# Power.net
KiCad netlist of a schematic drawn in Altium Designer
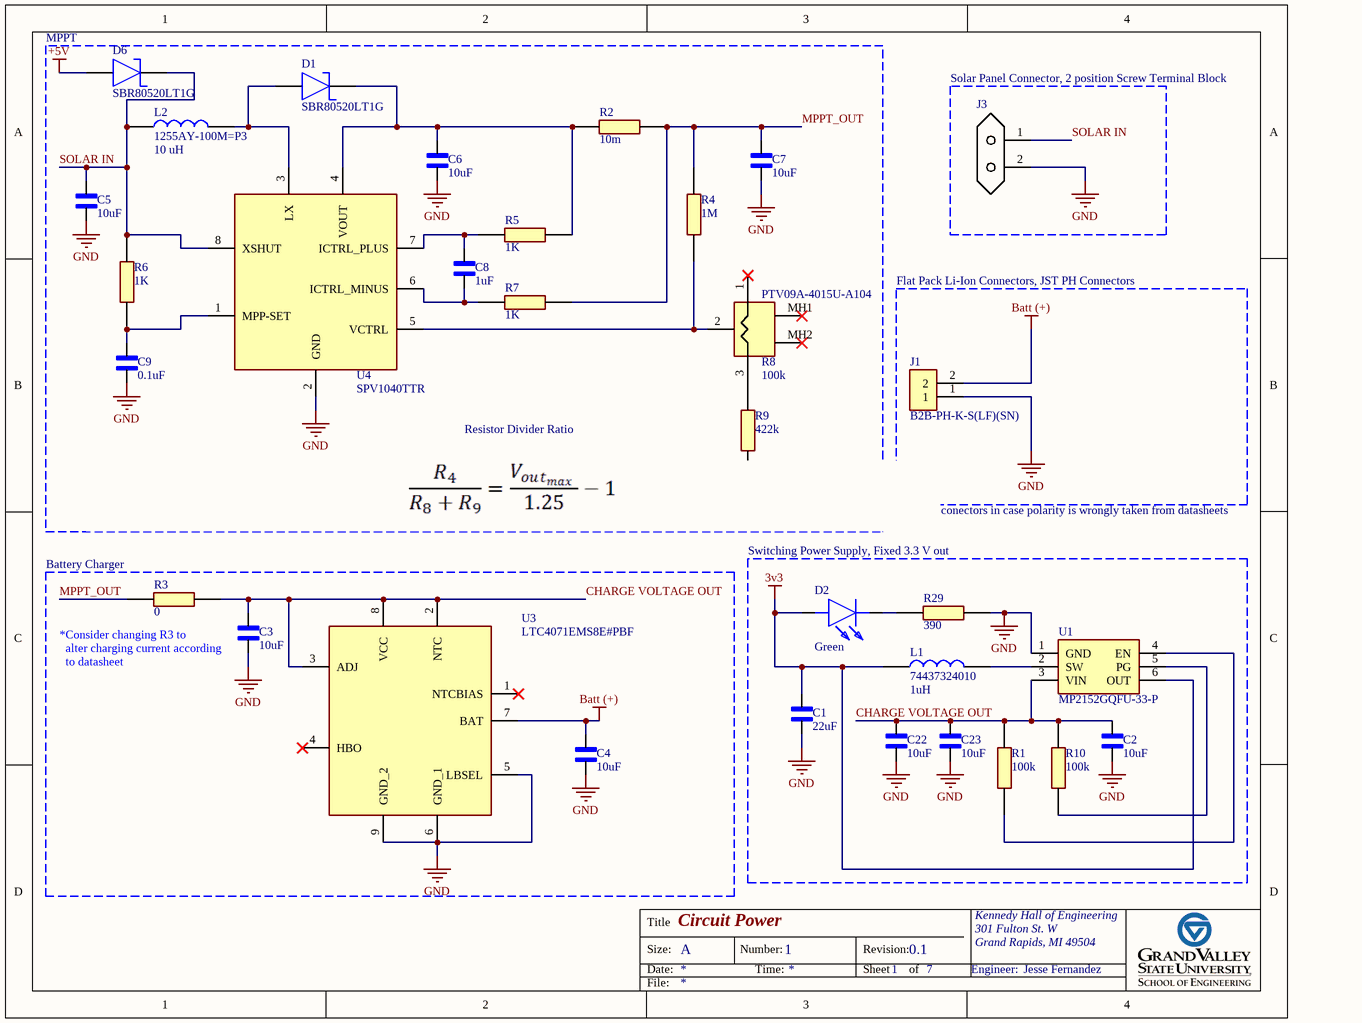
[diagram p0: Power.SchDoc]

(export (version "E")
  (design (tool "Eeschema 10.0.6"))
  (components
    (comp (ref "C1")
      (value "22uF")
      (footprint "CAPC1005X55N")
      (description "Capacitor X6S 0402 (1005 Metric)")
      (fields (field (name "MANUFACTURER") "Samsung Electro-Mechanics") (field (name "TOLERANCE") "20%"))
      (libsource (lib "UngBung") (part "Multilayer Ceramic Cap. 0402 (1005 Metric)"))
    )
    (comp (ref "C2")
      (value "10uF")
      (footprint "CAPC1005X55N")
      (description "Capacitor X6S 0402 (1005 Metric)")
      (fields (field (name "MANUFACTURER") "Murata Electronics") (field (name "TOLERANCE") "20%"))
      (libsource (lib "UngBung") (part "Multilayer Ceramic Cap. 0402 (1005 Metric)"))
    )
    (comp (ref "C3")
      (value "10uF")
      (footprint "CAPC1005X55N")
      (description "Capacitor X6S 0402 (1005 Metric)")
      (fields (field (name "MANUFACTURER") "Murata Electronics") (field (name "TOLERANCE") "20%"))
      (libsource (lib "UngBung") (part "Multilayer Ceramic Cap. 0402 (1005 Metric)"))
    )
    (comp (ref "C4")
      (value "10uF")
      (footprint "CAPC1005X55N")
      (description "Capacitor X6S 0402 (1005 Metric)")
      (fields (field (name "MANUFACTURER") "Murata Electronics") (field (name "TOLERANCE") "20%"))
      (libsource (lib "UngBung") (part "Multilayer Ceramic Cap. 0402 (1005 Metric)"))
    )
    (comp (ref "C5")
      (value "10uF")
      (footprint "CAPC1005X55N")
      (description "Capacitor X6S 0402 (1005 Metric)")
      (fields (field (name "MANUFACTURER") "Murata Electronics") (field (name "TOLERANCE") "20%"))
      (libsource (lib "UngBung") (part "Multilayer Ceramic Cap. 0402 (1005 Metric)"))
    )
    (comp (ref "C6")
      (value "10uF")
      (footprint "CAPC1005X55N")
      (description "Capacitor X6S 0402 (1005 Metric)")
      (fields (field (name "MANUFACTURER") "Murata Electronics") (field (name "TOLERANCE") "20%"))
      (libsource (lib "UngBung") (part "Multilayer Ceramic Cap. 0402 (1005 Metric)"))
    )
    (comp (ref "C7")
      (value "10uF")
      (footprint "CAPC1005X55N")
      (description "Capacitor X6S 0402 (1005 Metric)")
      (fields (field (name "MANUFACTURER") "Murata Electronics") (field (name "TOLERANCE") "20%"))
      (libsource (lib "UngBung") (part "Multilayer Ceramic Cap. 0402 (1005 Metric)"))
    )
    (comp (ref "C8")
      (value "1uF")
      (footprint "CAPC1005X55N")
      (description "Capacitor X6S 0402 (1005 Metric)")
      (fields (field (name "MANUFACTURER") "Murata Electronics") (field (name "TOLERANCE") "10%"))
      (libsource (lib "UngBung") (part "Multilayer Ceramic Cap. 0402 (1005 Metric)"))
    )
    (comp (ref "C9")
      (value "0.1uF")
      (footprint "CAPC1005X55N")
      (description "Capacitor X6S 0402 (1005 Metric)")
      (fields (field (name "MANUFACTURER") "Murata Electronics") (field (name "TOLERANCE") "10%"))
      (libsource (lib "UngBung") (part "Multilayer Ceramic Cap. 0402 (1005 Metric)"))
    )
    (comp (ref "C22")
      (value "10uF")
      (footprint "CAPC1005X55N")
      (description "Capacitor X6S 0402 (1005 Metric)")
      (fields (field (name "MANUFACTURER") "Murata Electronics") (field (name "TOLERANCE") "20%"))
      (libsource (lib "UngBung") (part "Multilayer Ceramic Cap. 0402 (1005 Metric)"))
    )
    (comp (ref "C23")
      (value "10uF")
      (footprint "CAPC1005X55N")
      (description "Capacitor X6S 0402 (1005 Metric)")
      (fields (field (name "MANUFACTURER") "Murata Electronics") (field (name "TOLERANCE") "20%"))
      (libsource (lib "UngBung") (part "Multilayer Ceramic Cap. 0402 (1005 Metric)"))
    )
    (comp (ref "D1")
      (value "SBR80520LT1G")
      (footprint "Diode SOD-123-2")
      (description "Schottky Diodes & Rectifiers REC SPCL SKTKY")
      (fields (field (name "MANUFACTURER") "ON Semiconductor"))
      (libsource (lib "UngBung") (part "SBR80520LT1G"))
    )
    (comp (ref "D2")
      (value "SML-LX0201UPGC-TR")
      (footprint "SML-LX0201UPGC-TR")
      (description "Standard LEDs - SMD 0201 SMD LEDs 520nm Green")
      (fields (field (name "MANUFACTURER") "Lumex") (field (name "COLOR") "Green"))
      (libsource (lib "UngBung") (part "SML-LX0201UPGC-TR"))
    )
    (comp (ref "D6")
      (value "SBR80520LT1G")
      (footprint "Diode SOD-123-2")
      (description "Schottky Diodes & Rectifiers REC SPCL SKTKY")
      (fields (field (name "MANUFACTURER") "ON Semiconductor"))
      (libsource (lib "UngBung") (part "SBR80520LT1G"))
    )
    (comp (ref "J1")
      (value "B2B-PH-K-S(LF)(SN)")
      (footprint "B2B-PH-K-S(LF)(SN)")
      (description "Connector Header Through Hole 2 position 0.079\" (2.00mm)")
      (fields (field (name "MANUFACTURER") "JST Sales America Inc."))
      (libsource (lib "UngBung") (part "B2B-PH-K-S(LF)(SN)"))
    )
    (comp (ref "J3")
      (value "Two-Position Terminal Block")
      (footprint "TB001-500-02BE")
      (fields (field (name "MANUFACTURER") "CUI Devices"))
      (libsource (lib "UngBung") (part "TB001-500-02BE"))
    )
    (comp (ref "L1")
      (value "74437324010")
      (footprint "Shielded Power Inductor")
      (description "Shieled Power Inductor")
      (fields (field (name "MANUFACTURER") "Wurth Elektronik") (field (name "ALTIUM_VALUE") "1uH"))
      (libsource (lib "UngBung") (part "74437324010"))
    )
    (comp (ref "L2")
      (value "1255AY-100M=P3")
      (footprint "1255AY-100M=P3")
      (description "Fixed Inductors 10uH 56.4mOhms3.1A +/-20% 6.3x6.3x4.5mm")
      (fields (field (name "MANUFACTURER") "Murata Electronics") (field (name "ALTIUM_VALUE") "10 uH"))
      (libsource (lib "UngBung") (part "1255AY-100M=P3"))
    )
    (comp (ref "R1")
      (value "100k")
      (footprint "Thin-Film Resistor 0402 (1005 Metric)")
      (description "Resistor, 0402 Package size")
      (fields (field (name "MANUFACTURER") "Vishay / Dale") (field (name "TOLERANCE") "1%"))
      (libsource (lib "UngBung") (part "Resistor 0402 (1005 Metric)"))
    )
    (comp (ref "R2")
      (value "10m")
      (footprint "Thin-Film Resistor 0402 (1005 Metric)")
      (description "Resistor, 0402 Package size")
      (fields (field (name "MANUFACTURER") "Panasonic") (field (name "TOLERANCE") "1%"))
      (libsource (lib "") (part "Resistor 0402 (1005 Metric)_1"))
    )
    (comp (ref "R3")
      (value "0")
      (footprint "Resistor 0603")
      (fields
        (field (name "MANUFACTURER") "Vishay / Dale")
        (field (name "TOLERANCE") "*tolerance*")
        (field (name "Comment") "Resistor 0603")
      )
      (libsource (lib "UngBung") (part "Resistor 0603"))
    )
    (comp (ref "R4")
      (value "1M")
      (footprint "Thin-Film Resistor 0402 (1005 Metric)")
      (description "Resistor, 0402 Package size")
      (fields (field (name "MANUFACTURER") "Vishay / Dale") (field (name "TOLERANCE") "1%"))
      (libsource (lib "UngBung") (part "Resistor 0402 (1005 Metric)"))
    )
    (comp (ref "R5")
      (value "1K")
      (footprint "Thin-Film Resistor 0402 (1005 Metric)")
      (description "Resistor, 0402 Package size")
      (fields (field (name "MANUFACTURER") "Vishay / Dale") (field (name "TOLERANCE") "1%"))
      (libsource (lib "") (part "Resistor 0402 (1005 Metric)_2"))
    )
    (comp (ref "R6")
      (value "1K")
      (footprint "Thin-Film Resistor 0402 (1005 Metric)")
      (description "Resistor, 0402 Package size")
      (fields (field (name "MANUFACTURER") "Vishay / Dale") (field (name "TOLERANCE") "1%"))
      (libsource (lib "UngBung") (part "Resistor 0402 (1005 Metric)"))
    )
    (comp (ref "R7")
      (value "1K")
      (footprint "Thin-Film Resistor 0402 (1005 Metric)")
      (description "Resistor, 0402 Package size")
      (fields (field (name "MANUFACTURER") "Vishay / Dale") (field (name "TOLERANCE") "1%"))
      (libsource (lib "") (part "Resistor 0402 (1005 Metric)_2"))
    )
    (comp (ref "R8")
      (value "PTV09A-4015U-A104")
      (footprint "PTV09A-4015U-A104")
      (description "Potentiometers PANEL CONTROL - 9MM-ST-CA 100 kohms 15 mm")
      (fields (field (name "MANUFACTURER") "Bourns") (field (name "ALTIUM_VALUE") "100k"))
      (libsource (lib "UngBung") (part "PTV09A-4015U-A104"))
    )
    (comp (ref "R9")
      (value "422k")
      (footprint "Thin-Film Resistor 0402 (1005 Metric)")
      (description "Resistor, 0402 Package size")
      (fields (field (name "MANUFACTURER") "Panasonic") (field (name "TOLERANCE") "1%"))
      (libsource (lib "UngBung") (part "Resistor 0402 (1005 Metric)"))
    )
    (comp (ref "R10")
      (value "100k")
      (footprint "Thin-Film Resistor 0402 (1005 Metric)")
      (description "Resistor, 0402 Package size")
      (fields (field (name "MANUFACTURER") "Vishay / Dale") (field (name "TOLERANCE") "1%"))
      (libsource (lib "UngBung") (part "Resistor 0402 (1005 Metric)"))
    )
    (comp (ref "R29")
      (value "390")
      (footprint "Thin-Film Resistor 0402 (1005 Metric)")
      (description "Resistor, 0402 Package size")
      (fields (field (name "MANUFACTURER") "Yageo") (field (name "TOLERANCE") "1%"))
      (libsource (lib "") (part "Resistor 0402 (1005 Metric)_1"))
    )
    (comp (ref "U1")
      (value "MP2152GQFU-33-P")
      (footprint "MP2152GQFU-33-P")
      (fields (field (name "MANUFACTURER") "Monolithic Power Systems (MPS)"))
      (libsource (lib "UngBung") (part "MP2152GQFU-33-P"))
    )
    (comp (ref "U3")
      (value "LTC4071EMS8E#PBF")
      (footprint "LTC4071EMS8E#PBF")
      (description "Battery Management Li-Ion/Polymer Shunt Battery Charger System with Low Battery Disconnect")
      (fields (field (name "MANUFACTURER") "Analog Devices"))
      (libsource (lib "UngBung") (part "LTC4071EMS8E#PBF"))
    )
    (comp (ref "U4")
      (value "SPV1040TTR")
      (footprint "SPV1040TTR")
      (description "Switching Voltage Regulators Hi Eff Solar Charger MPPT 0.3V to 5.5V")
      (fields (field (name "MANUFACTURER") "STMicroelectronics"))
      (libsource (lib "UngBung") (part "SPV1040TTR"))
    )
  )
  (nets
    (net (code "1") (name "+5V") (class "Default")
      (node (ref "D6") (pin "2") (pinfunction "A_2") (pintype "passive"))
    )
    (net (code "3") (name "/CHARGE VOLTAGE OUT") (class "Default")
      (node (ref "C2") (pin "2") (pinfunction "2_2") (pintype "passive"))
      (node (ref "C22") (pin "2") (pinfunction "2_2") (pintype "passive"))
      (node (ref "C23") (pin "2") (pinfunction "2_2") (pintype "passive"))
      (node (ref "C3") (pin "2") (pinfunction "2_2") (pintype "passive"))
      (node (ref "R1") (pin "2") (pinfunction "2_2") (pintype "passive"))
      (node (ref "R10") (pin "2") (pinfunction "2_2") (pintype "passive"))
      (node (ref "R3") (pin "2") (pinfunction "2_2") (pintype "passive"))
      (node (ref "U1") (pin "3") (pinfunction "VIN_3") (pintype "passive"))
      (node (ref "U3") (pin "2") (pinfunction "NTC_2") (pintype "passive"))
      (node (ref "U3") (pin "3") (pinfunction "ADJ_3") (pintype "passive"))
      (node (ref "U3") (pin "8") (pinfunction "VCC_8") (pintype "passive"))
    )
    (net (code "4") (name "/MPPT_OUT") (class "Default")
      (node (ref "C7") (pin "2") (pinfunction "2_2") (pintype "passive"))
      (node (ref "R2") (pin "2") (pinfunction "2_2") (pintype "passive"))
      (node (ref "R3") (pin "1") (pinfunction "1_1") (pintype "passive"))
      (node (ref "R4") (pin "2") (pinfunction "2_2") (pintype "passive"))
      (node (ref "R7") (pin "1") (pinfunction "1_1") (pintype "passive"))
    )
    (net (code "5") (name "/SOLAR IN") (class "Default")
      (node (ref "C5") (pin "2") (pinfunction "2_2") (pintype "passive"))
      (node (ref "D6") (pin "1") (pinfunction "K_1") (pintype "passive"))
      (node (ref "J3") (pin "1") (pinfunction "1_1") (pintype "passive"))
      (node (ref "L2") (pin "1") (pinfunction "1_1") (pintype "passive"))
      (node (ref "R6") (pin "2") (pinfunction "2_2") (pintype "passive"))
      (node (ref "U4") (pin "8") (pinfunction "XSHUT_8") (pintype "passive"))
    )
    (net (code "6") (name "3v3") (class "Default")
      (node (ref "C1") (pin "2") (pinfunction "2_2") (pintype "passive"))
      (node (ref "D2") (pin "2") (pinfunction "A_2") (pintype "passive"))
      (node (ref "L1") (pin "1") (pinfunction "1_1") (pintype "passive"))
      (node (ref "U1") (pin "6") (pinfunction "OUT_6") (pintype "passive"))
    )
    (net (code "7") (name "Batt (+)") (class "Default")
      (node (ref "C4") (pin "2") (pinfunction "2_2") (pintype "passive"))
      (node (ref "J1") (pin "2") (pinfunction "2_2") (pintype "passive"))
      (node (ref "U3") (pin "7") (pinfunction "BAT_7") (pintype "passive"))
    )
    (net (code "8") (name "GND") (class "Default")
      (node (ref "C1") (pin "1") (pinfunction "1_1") (pintype "passive"))
      (node (ref "C2") (pin "1") (pinfunction "1_1") (pintype "passive"))
      (node (ref "C22") (pin "1") (pinfunction "1_1") (pintype "passive"))
      (node (ref "C23") (pin "1") (pinfunction "1_1") (pintype "passive"))
      (node (ref "C3") (pin "1") (pinfunction "1_1") (pintype "passive"))
      (node (ref "C4") (pin "1") (pinfunction "1_1") (pintype "passive"))
      (node (ref "C5") (pin "1") (pinfunction "1_1") (pintype "passive"))
      (node (ref "C6") (pin "1") (pinfunction "1_1") (pintype "passive"))
      (node (ref "C7") (pin "1") (pinfunction "1_1") (pintype "passive"))
      (node (ref "C9") (pin "1") (pinfunction "1_1") (pintype "passive"))
      (node (ref "J1") (pin "1") (pinfunction "1_1") (pintype "passive"))
      (node (ref "J3") (pin "2") (pinfunction "2_2") (pintype "passive"))
      (node (ref "R29") (pin "2") (pinfunction "2_2") (pintype "passive"))
      (node (ref "R9") (pin "1") (pinfunction "1_1") (pintype "passive"))
      (node (ref "U1") (pin "1") (pinfunction "GND_1") (pintype "passive"))
      (node (ref "U3") (pin "5") (pinfunction "LBSEL_5") (pintype "passive"))
      (node (ref "U3") (pin "6") (pinfunction "GND_1_6") (pintype "passive"))
      (node (ref "U3") (pin "9") (pinfunction "GND_2_9") (pintype "passive"))
      (node (ref "U4") (pin "2") (pinfunction "GND_2") (pintype "power_in"))
    )
    (net (code "9") (name "Net-(D1-A)") (class "Default")
      (node (ref "D1") (pin "2") (pinfunction "A_2") (pintype "passive"))
      (node (ref "L2") (pin "2") (pinfunction "2_2") (pintype "passive"))
      (node (ref "U4") (pin "3") (pinfunction "LX_3") (pintype "passive"))
    )
    (net (code "10") (name "Net-(D1-K)") (class "Default")
      (node (ref "C6") (pin "2") (pinfunction "2_2") (pintype "passive"))
      (node (ref "D1") (pin "1") (pinfunction "K_1") (pintype "passive"))
      (node (ref "R2") (pin "1") (pinfunction "1_1") (pintype "passive"))
      (node (ref "R5") (pin "1") (pinfunction "1_1") (pintype "passive"))
      (node (ref "U4") (pin "4") (pinfunction "VOUT_4") (pintype "passive"))
    )
    (net (code "11") (name "Net-(D2-K)") (class "Default")
      (node (ref "D2") (pin "1") (pinfunction "K_1") (pintype "passive"))
      (node (ref "R29") (pin "1") (pinfunction "1_1") (pintype "passive"))
    )
    (net (code "12") (name "Net-(R8-CW)") (class "Default")
      (node (ref "R8") (pin "3") (pinfunction "CW_3") (pintype "passive"))
      (node (ref "R9") (pin "2") (pinfunction "2_2") (pintype "passive"))
    )
    (net (code "13") (name "Net-(R8-WIPER)") (class "Default")
      (node (ref "R4") (pin "1") (pinfunction "1_1") (pintype "passive"))
      (node (ref "R8") (pin "2") (pinfunction "WIPER_2") (pintype "passive"))
      (node (ref "U4") (pin "5") (pinfunction "VCTRL_5") (pintype "passive"))
    )
    (net (code "14") (name "Net-(U1-EN)") (class "Default")
      (node (ref "R1") (pin "1") (pinfunction "1_1") (pintype "passive"))
      (node (ref "U1") (pin "4") (pinfunction "EN_4") (pintype "passive"))
    )
    (net (code "15") (name "Net-(U1-PG)") (class "Default")
      (node (ref "R10") (pin "1") (pinfunction "1_1") (pintype "passive"))
      (node (ref "U1") (pin "5") (pinfunction "PG_5") (pintype "passive"))
    )
    (net (code "16") (name "Net-(U1-SW)") (class "Default")
      (node (ref "L1") (pin "2") (pinfunction "2_2") (pintype "passive"))
      (node (ref "U1") (pin "2") (pinfunction "SW_2") (pintype "passive"))
    )
    (net (code "17") (name "Net-(U4-ICTRL_MINUS)") (class "Default")
      (node (ref "C8") (pin "1") (pinfunction "1_1") (pintype "passive"))
      (node (ref "R7") (pin "2") (pinfunction "2_2") (pintype "passive"))
      (node (ref "U4") (pin "6") (pinfunction "ICTRL_MINUS_6") (pintype "passive"))
    )
    (net (code "18") (name "Net-(U4-ICTRL_PLUS)") (class "Default")
      (node (ref "C8") (pin "2") (pinfunction "2_2") (pintype "passive"))
      (node (ref "R5") (pin "2") (pinfunction "2_2") (pintype "passive"))
      (node (ref "U4") (pin "7") (pinfunction "ICTRL_PLUS_7") (pintype "passive"))
    )
    (net (code "19") (name "Net-(U4-MPP-SET)") (class "Default")
      (node (ref "C9") (pin "2") (pinfunction "2_2") (pintype "passive"))
      (node (ref "R6") (pin "1") (pinfunction "1_1") (pintype "passive"))
      (node (ref "U4") (pin "1") (pinfunction "MPP-SET_1") (pintype "passive"))
    )
    (net (code "20") (name "unconnected-(R8-CCW-Pad1)") (class "Default")
      (node (ref "R8") (pin "1") (pinfunction "CCW_1") (pintype "passive+no_connect"))
    )
    (net (code "21") (name "unconnected-(R8-PadMH1)") (class "Default")
      (node (ref "R8") (pin "MH1") (pinfunction "MH1_MH1") (pintype "passive+no_connect"))
    )
    (net (code "22") (name "unconnected-(R8-PadMH2)") (class "Default")
      (node (ref "R8") (pin "MH2") (pinfunction "MH2_MH2") (pintype "passive+no_connect"))
    )
    (net (code "23") (name "unconnected-(U3-HBO-Pad4)") (class "Default")
      (node (ref "U3") (pin "4") (pinfunction "HBO_4") (pintype "passive+no_connect"))
    )
    (net (code "24") (name "unconnected-(U3-NTCBIAS-Pad1)") (class "Default")
      (node (ref "U3") (pin "1") (pinfunction "NTCBIAS_1") (pintype "passive+no_connect"))
    )
  )
)
